# Multiple_Buck_Converter.net
KiCad netlist of a schematic drawn in Altium Designer
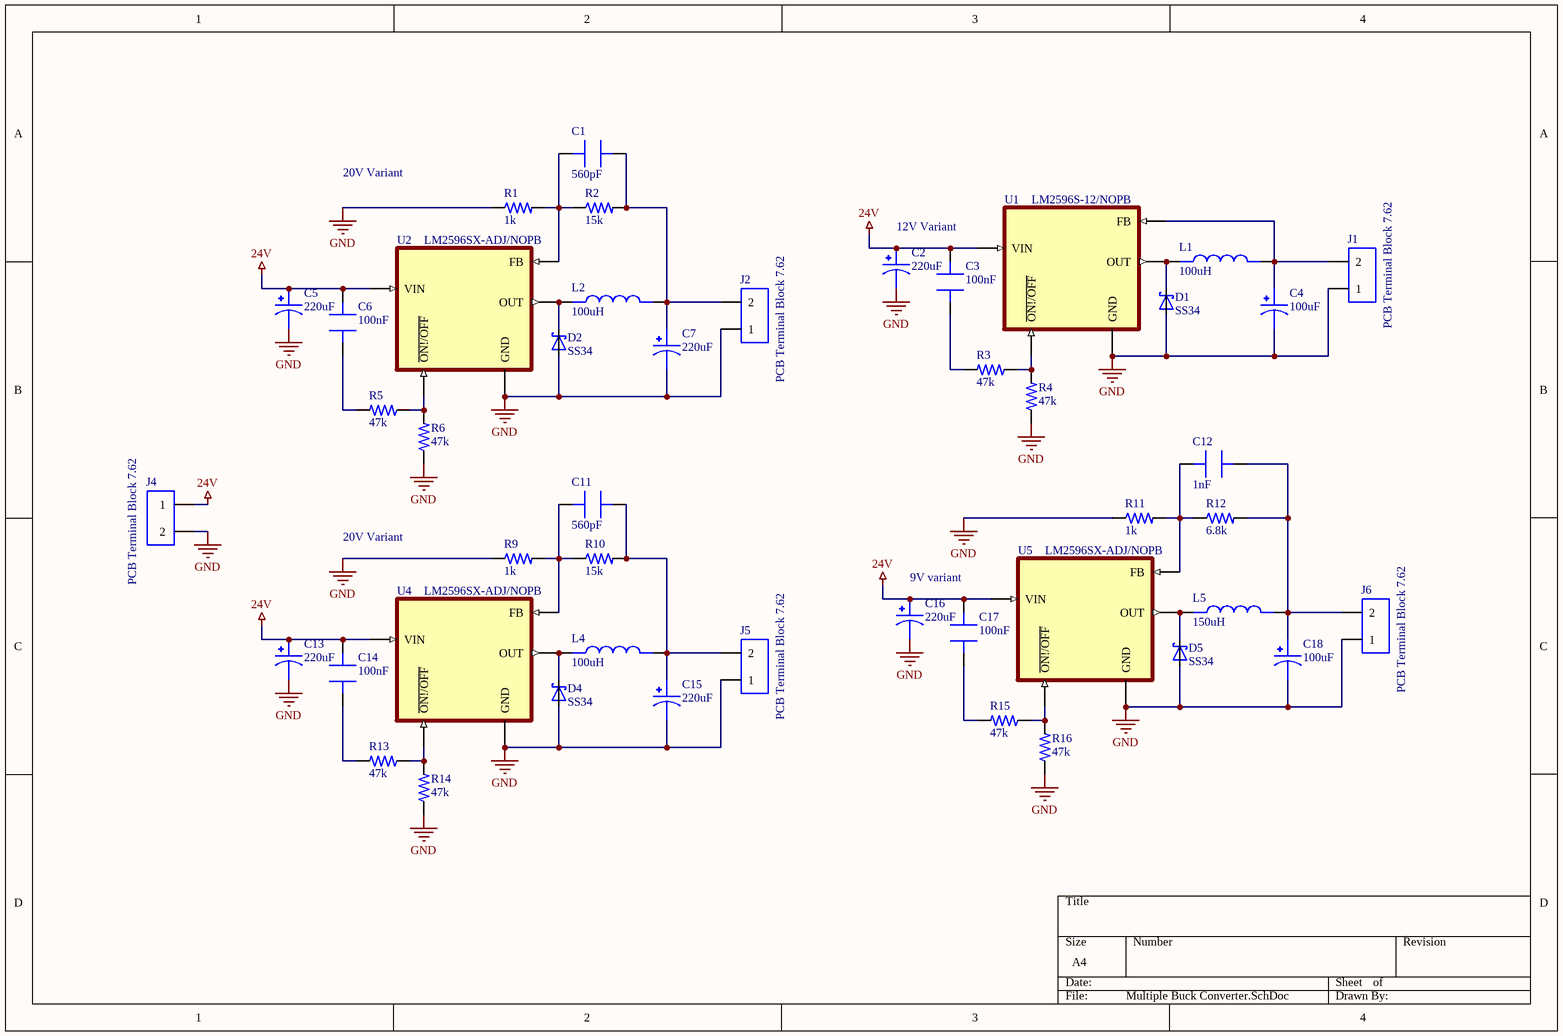
[diagram p0: Multiple Buck Converter.SchDoc]

(export (version "E")
  (design (tool "Eeschema 10.0.6"))
  (components
    (comp (ref "C1")
      (value "560pF")
      (footprint "C0805")
      (description "100V 560pF NP0 ±2% 0805 Multilayer Ceramic Capacitors MLCC - SMD/SMT ROHS")
      (fields
        (field (name "MANUFACTURER") "YAGEO")
        (field (name "MANUFACTURER PART NUMBER") "CC0805GRNPO0BN561")
      )
      (libsource (lib "Multiple Buck Converter") (part "CC0805GRNPO0BN561"))
    )
    (comp (ref "C2")
      (value "220uF")
      (footprint "CAPAE1030X1080N")
      (fields
        (field (name "MANUFACTURER") "Nichicon")
        (field (name "MANUFACTURER PART NUMBER") "UUD1H221MNL1GS")
      )
      (libsource (lib "Multiple Buck Converter") (part "UUD1H221MNL1GS"))
    )
    (comp (ref "C3")
      (value "100nF")
      (footprint "CAP_1206")
      (description "50V 100nF X7R ±10% 1206 Multilayer Ceramic Capacitors MLCC - SMD/SMT ROHS")
      (fields
        (field (name "MANUFACTURER") "YAGEO")
        (field (name "MANUFACTURER PART NUMBER") "CC1206KRX7R9BB104")
      )
      (libsource (lib "Multiple Buck Converter") (part "CC1206KRX7R9BB104"))
    )
    (comp (ref "C4")
      (value "100uF")
      (footprint "CAPPM7343X310N")
      (description "100uF 10V -55℃~+125℃ 50mΩ@100kHz ±10% CASE-D_7343 Tantalum Capacitors ROHS")
      (fields
        (field (name "MANUFACTURER") "Kyocera AVX")
        (field (name "MANUFACTURER PART NUMBER") "TPSD107K010R0050")
      )
      (libsource (lib "Multiple Buck Converter") (part "TPSD107K010R0050"))
    )
    (comp (ref "C5")
      (value "220uF")
      (footprint "CAPAE1030X1080N")
      (fields
        (field (name "MANUFACTURER") "Nichicon")
        (field (name "MANUFACTURER PART NUMBER") "UUD1H221MNL1GS")
      )
      (libsource (lib "Multiple Buck Converter") (part "UUD1H221MNL1GS"))
    )
    (comp (ref "C6")
      (value "100nF")
      (footprint "CAP_1206")
      (description "50V 100nF X7R ±10% 1206 Multilayer Ceramic Capacitors MLCC - SMD/SMT ROHS")
      (fields
        (field (name "MANUFACTURER") "YAGEO")
        (field (name "MANUFACTURER PART NUMBER") "CC1206KRX7R9BB104")
      )
      (libsource (lib "Multiple Buck Converter") (part "CC1206KRX7R9BB104"))
    )
    (comp (ref "C7")
      (value "220uF")
      (footprint "CAPAE1030X1080N")
      (fields
        (field (name "MANUFACTURER") "Nichicon")
        (field (name "MANUFACTURER PART NUMBER") "UUD1H221MNL1GS")
      )
      (libsource (lib "Multiple Buck Converter") (part "UUD1H221MNL1GS"))
    )
    (comp (ref "C11")
      (value "560pF")
      (footprint "C0805")
      (description "100V 560pF NP0 ±2% 0805 Multilayer Ceramic Capacitors MLCC - SMD/SMT ROHS")
      (fields
        (field (name "MANUFACTURER") "YAGEO")
        (field (name "MANUFACTURER PART NUMBER") "CC0805GRNPO0BN561")
      )
      (libsource (lib "Multiple Buck Converter") (part "CC0805GRNPO0BN561"))
    )
    (comp (ref "C12")
      (value "1nF")
      (footprint "CAP_1206")
      (description "2kV 1nF X7R ±10% 1206 Multilayer Ceramic Capacitors MLCC - SMD/SMT ROHS")
      (fields
        (field (name "MANUFACTURER") "YAGEO")
        (field (name "MANUFACTURER PART NUMBER") "CC1206KKX7RDBB102")
      )
      (libsource (lib "Multiple Buck Converter") (part "CC1206KKX7RDBB102"))
    )
    (comp (ref "C13")
      (value "220uF")
      (footprint "CAPAE1030X1080N")
      (fields
        (field (name "MANUFACTURER") "Nichicon")
        (field (name "MANUFACTURER PART NUMBER") "UUD1H221MNL1GS")
      )
      (libsource (lib "Multiple Buck Converter") (part "UUD1H221MNL1GS"))
    )
    (comp (ref "C14")
      (value "100nF")
      (footprint "CAP_1206")
      (description "50V 100nF X7R ±10% 1206 Multilayer Ceramic Capacitors MLCC - SMD/SMT ROHS")
      (fields
        (field (name "MANUFACTURER") "YAGEO")
        (field (name "MANUFACTURER PART NUMBER") "CC1206KRX7R9BB104")
      )
      (libsource (lib "Multiple Buck Converter") (part "CC1206KRX7R9BB104"))
    )
    (comp (ref "C15")
      (value "220uF")
      (footprint "CAPAE1030X1080N")
      (fields
        (field (name "MANUFACTURER") "Nichicon")
        (field (name "MANUFACTURER PART NUMBER") "UUD1H221MNL1GS")
      )
      (libsource (lib "Multiple Buck Converter") (part "UUD1H221MNL1GS"))
    )
    (comp (ref "C16")
      (value "220uF")
      (footprint "CAPAE1030X1080N")
      (fields
        (field (name "MANUFACTURER") "Nichicon")
        (field (name "MANUFACTURER PART NUMBER") "UUD1H221MNL1GS")
      )
      (libsource (lib "Multiple Buck Converter") (part "UUD1H221MNL1GS"))
    )
    (comp (ref "C17")
      (value "100nF")
      (footprint "CAP_1206")
      (description "50V 100nF X7R ±10% 1206 Multilayer Ceramic Capacitors MLCC - SMD/SMT ROHS")
      (fields
        (field (name "MANUFACTURER") "YAGEO")
        (field (name "MANUFACTURER PART NUMBER") "CC1206KRX7R9BB104")
      )
      (libsource (lib "Multiple Buck Converter") (part "CC1206KRX7R9BB104"))
    )
    (comp (ref "C18")
      (value "100uF")
      (footprint "CAPPM6032X280N")
      (description "100uF 16V -55℃~+125℃ 1Ω@100kHz ±20% CASE-C_6032 Tantalum Capacitors ROHS")
      (fields
        (field (name "MANUFACTURER") "Hunan Xiangyee in S&T")
        (field (name "MANUFACTURER PART NUMBER") "CA45-C016M107T")
      )
      (libsource (lib "Multiple Buck Converter") (part "CA45-C016M107T"))
    )
    (comp (ref "D1")
      (value "SS34")
      (footprint "SS34-1")
      (description "0.5mA@40V 40V Single 3A 0.55V@3A SMA(DO-214AC) Schottky Barrier Diodes (SBD) ROHS")
      (fields (field (name "MANUFACTURER") "MDD (Microdiode Electronics)"))
      (libsource (lib "Multiple Buck Converter") (part "SS34"))
    )
    (comp (ref "D2")
      (value "SS34")
      (footprint "SS34-1")
      (description "0.5mA@40V 40V Single 3A 0.55V@3A SMA(DO-214AC) Schottky Barrier Diodes (SBD) ROHS")
      (fields (field (name "MANUFACTURER") "MDD (Microdiode Electronics)"))
      (libsource (lib "Multiple Buck Converter") (part "SS34"))
    )
    (comp (ref "D4")
      (value "SS34")
      (footprint "SS34-1")
      (description "0.5mA@40V 40V Single 3A 0.55V@3A SMA(DO-214AC) Schottky Barrier Diodes (SBD) ROHS")
      (fields (field (name "MANUFACTURER") "MDD (Microdiode Electronics)"))
      (libsource (lib "Multiple Buck Converter") (part "SS34"))
    )
    (comp (ref "D5")
      (value "SS34")
      (footprint "SS34-1")
      (description "0.5mA@40V 40V Single 3A 0.55V@3A SMA(DO-214AC) Schottky Barrier Diodes (SBD) ROHS")
      (fields (field (name "MANUFACTURER") "MDD (Microdiode Electronics)"))
      (libsource (lib "Multiple Buck Converter") (part "SS34"))
    )
    (comp (ref "J1")
      (value "PCB Terminal Block 7.62")
      (footprint "KF25C-7.62-2P")
      (fields
        (field (name "MANUFACTURER") "Cixi Kefa Elec")
        (field (name "MANUFACTURER PART NUMBER") "KF25C-7.62-2P")
      )
      (libsource (lib "Multiple Buck Converter") (part "KF25C-7.62-2P"))
    )
    (comp (ref "J2")
      (value "PCB Terminal Block 7.62")
      (footprint "KF25C-7.62-2P")
      (fields
        (field (name "MANUFACTURER") "Cixi Kefa Elec")
        (field (name "MANUFACTURER PART NUMBER") "KF25C-7.62-2P")
      )
      (libsource (lib "Multiple Buck Converter") (part "KF25C-7.62-2P"))
    )
    (comp (ref "J4")
      (value "PCB Terminal Block 7.62")
      (footprint "KF25C-7.62-2P")
      (fields
        (field (name "MANUFACTURER") "Cixi Kefa Elec")
        (field (name "MANUFACTURER PART NUMBER") "KF25C-7.62-2P")
      )
      (libsource (lib "Multiple Buck Converter") (part "KF25C-7.62-2P"))
    )
    (comp (ref "J5")
      (value "PCB Terminal Block 7.62")
      (footprint "KF25C-7.62-2P")
      (fields
        (field (name "MANUFACTURER") "Cixi Kefa Elec")
        (field (name "MANUFACTURER PART NUMBER") "KF25C-7.62-2P")
      )
      (libsource (lib "Multiple Buck Converter") (part "KF25C-7.62-2P"))
    )
    (comp (ref "J6")
      (value "PCB Terminal Block 7.62")
      (footprint "KF25C-7.62-2P")
      (fields
        (field (name "MANUFACTURER") "Cixi Kefa Elec")
        (field (name "MANUFACTURER PART NUMBER") "KF25C-7.62-2P")
      )
      (libsource (lib "Multiple Buck Converter") (part "KF25C-7.62-2P"))
    )
    (comp (ref "L1")
      (value "100uH")
      (footprint "DS1207")
      (description "Shielded Inductor DS1207 100uH")
      (fields (field (name "MANUFACTURER") "SPORTON") (field (name "MANUFACTURER PART NUMBER") "SDS127"))
      (libsource (lib "Multiple Buck Converter") (part "DS1207_100uH"))
    )
    (comp (ref "L2")
      (value "100uH")
      (footprint "DS1207")
      (description "Shielded Inductor DS1207 100uH")
      (fields (field (name "MANUFACTURER") "SPORTON") (field (name "MANUFACTURER PART NUMBER") "SDS127"))
      (libsource (lib "Multiple Buck Converter") (part "DS1207_100uH"))
    )
    (comp (ref "L4")
      (value "100uH")
      (footprint "DS1207")
      (description "Shielded Inductor DS1207 100uH")
      (fields (field (name "MANUFACTURER") "SPORTON") (field (name "MANUFACTURER PART NUMBER") "SDS127"))
      (libsource (lib "Multiple Buck Converter") (part "DS1207_100uH"))
    )
    (comp (ref "L5")
      (value "150uH")
      (footprint "DS1207")
      (description "Shielded Inductor DS1207 47uH")
      (fields (field (name "MANUFACTURER") "SPORTON") (field (name "MANUFACTURER PART NUMBER") "SDS127"))
      (libsource (lib "Multiple Buck Converter") (part "DS1207_150uH"))
    )
    (comp (ref "R1")
      (value "1k")
      (footprint "RES_1206")
      (fields
        (field (name "MANUFACTURER") "YAGEO")
        (field (name "MANUFACTURER PART NUMBER") "RC1206FR-071KL")
      )
      (libsource (lib "Multiple Buck Converter") (part "RC1206FR-071KL"))
    )
    (comp (ref "R2")
      (value "15k")
      (footprint "RES_1206")
      (fields
        (field (name "MANUFACTURER") "YAGEO")
        (field (name "MANUFACTURER PART NUMBER") "RC1206FR-0715KL")
      )
      (libsource (lib "Multiple Buck Converter") (part "RC1206FR-0715KL"))
    )
    (comp (ref "R3")
      (value "47k")
      (footprint "RES_1206")
      (fields
        (field (name "MANUFACTURER") "YAGEO")
        (field (name "MANUFACTURER PART NUMBER") "RC1206FR-0747KL")
      )
      (libsource (lib "Multiple Buck Converter") (part "RC1206FR-0747KL"))
    )
    (comp (ref "R4")
      (value "47k")
      (footprint "RES_1206")
      (fields
        (field (name "MANUFACTURER") "YAGEO")
        (field (name "MANUFACTURER PART NUMBER") "RC1206FR-0747KL")
      )
      (libsource (lib "Multiple Buck Converter") (part "RC1206FR-0747KL"))
    )
    (comp (ref "R5")
      (value "47k")
      (footprint "RES_1206")
      (fields
        (field (name "MANUFACTURER") "YAGEO")
        (field (name "MANUFACTURER PART NUMBER") "RC1206FR-0747KL")
      )
      (libsource (lib "Multiple Buck Converter") (part "RC1206FR-0747KL"))
    )
    (comp (ref "R6")
      (value "47k")
      (footprint "RES_1206")
      (fields
        (field (name "MANUFACTURER") "YAGEO")
        (field (name "MANUFACTURER PART NUMBER") "RC1206FR-0747KL")
      )
      (libsource (lib "Multiple Buck Converter") (part "RC1206FR-0747KL"))
    )
    (comp (ref "R9")
      (value "1k")
      (footprint "RES_1206")
      (fields
        (field (name "MANUFACTURER") "YAGEO")
        (field (name "MANUFACTURER PART NUMBER") "RC1206FR-071KL")
      )
      (libsource (lib "Multiple Buck Converter") (part "RC1206FR-071KL"))
    )
    (comp (ref "R10")
      (value "15k")
      (footprint "RES_1206")
      (fields
        (field (name "MANUFACTURER") "YAGEO")
        (field (name "MANUFACTURER PART NUMBER") "RC1206FR-0715KL")
      )
      (libsource (lib "Multiple Buck Converter") (part "RC1206FR-0715KL"))
    )
    (comp (ref "R11")
      (value "1k")
      (footprint "RES_1206")
      (fields
        (field (name "MANUFACTURER") "YAGEO")
        (field (name "MANUFACTURER PART NUMBER") "RC1206FR-071KL")
      )
      (libsource (lib "Multiple Buck Converter") (part "RC1206FR-071KL"))
    )
    (comp (ref "R12")
      (value "6.8k")
      (footprint "RES_1206")
      (fields
        (field (name "MANUFACTURER") "YAGEO")
        (field (name "MANUFACTURER PART NUMBER") "RC1206FR-076K8L")
      )
      (libsource (lib "Multiple Buck Converter") (part "RC1206FR-076K8L"))
    )
    (comp (ref "R13")
      (value "47k")
      (footprint "RES_1206")
      (fields
        (field (name "MANUFACTURER") "YAGEO")
        (field (name "MANUFACTURER PART NUMBER") "RC1206FR-0747KL")
      )
      (libsource (lib "Multiple Buck Converter") (part "RC1206FR-0747KL"))
    )
    (comp (ref "R14")
      (value "47k")
      (footprint "RES_1206")
      (fields
        (field (name "MANUFACTURER") "YAGEO")
        (field (name "MANUFACTURER PART NUMBER") "RC1206FR-0747KL")
      )
      (libsource (lib "Multiple Buck Converter") (part "RC1206FR-0747KL"))
    )
    (comp (ref "R15")
      (value "47k")
      (footprint "RES_1206")
      (fields
        (field (name "MANUFACTURER") "YAGEO")
        (field (name "MANUFACTURER PART NUMBER") "RC1206FR-0747KL")
      )
      (libsource (lib "Multiple Buck Converter") (part "RC1206FR-0747KL"))
    )
    (comp (ref "R16")
      (value "47k")
      (footprint "RES_1206")
      (fields
        (field (name "MANUFACTURER") "YAGEO")
        (field (name "MANUFACTURER PART NUMBER") "RC1206FR-0747KL")
      )
      (libsource (lib "Multiple Buck Converter") (part "RC1206FR-0747KL"))
    )
    (comp (ref "U1")
      (value "LM2596S-12/NOPB")
      (footprint "VREG_LM2596SX-ADJ/NOPB")
      (fields (field (name "MANUFACTURER") "Texas Instruments"))
      (libsource (lib "Multiple Buck Converter") (part "LM2596SX-ADJ/NOPB"))
    )
    (comp (ref "U2")
      (value "LM2596SX-ADJ/NOPB")
      (footprint "VREG_LM2596SX-ADJ/NOPB")
      (fields
        (field (name "MANUFACTURER") "UMW(Youtai Semiconductor Co., Ltd.)")
        (field (name "MANUFACTURER PART NUMBER") "LM2596S-ADJ")
      )
      (libsource (lib "Multiple Buck Converter") (part "LM2596SX-ADJ/NOPB"))
    )
    (comp (ref "U4")
      (value "LM2596SX-ADJ/NOPB")
      (footprint "VREG_LM2596SX-ADJ/NOPB")
      (fields
        (field (name "MANUFACTURER") "UMW(Youtai Semiconductor Co., Ltd.)")
        (field (name "MANUFACTURER PART NUMBER") "LM2596S-ADJ")
      )
      (libsource (lib "Multiple Buck Converter") (part "LM2596SX-ADJ/NOPB"))
    )
    (comp (ref "U5")
      (value "LM2596SX-ADJ/NOPB")
      (footprint "VREG_LM2596SX-ADJ/NOPB")
      (fields
        (field (name "MANUFACTURER") "UMW(Youtai Semiconductor Co., Ltd.)")
        (field (name "MANUFACTURER PART NUMBER") "LM2596S-ADJ")
      )
      (libsource (lib "Multiple Buck Converter") (part "LM2596SX-ADJ/NOPB"))
    )
  )
  (nets
    (net (code "1") (name "24V") (class "Default")
      (node (ref "C13") (pin "1") (pinfunction "1_1") (pintype "passive"))
      (node (ref "C14") (pin "1") (pinfunction "PIN1_1") (pintype "passive"))
      (node (ref "C16") (pin "1") (pinfunction "1_1") (pintype "passive"))
      (node (ref "C17") (pin "1") (pinfunction "PIN1_1") (pintype "passive"))
      (node (ref "C2") (pin "1") (pinfunction "1_1") (pintype "passive"))
      (node (ref "C3") (pin "1") (pinfunction "PIN1_1") (pintype "passive"))
      (node (ref "C5") (pin "1") (pinfunction "1_1") (pintype "passive"))
      (node (ref "C6") (pin "1") (pinfunction "PIN1_1") (pintype "passive"))
      (node (ref "J4") (pin "1") (pinfunction "1_1") (pintype "passive"))
      (node (ref "U1") (pin "1") (pinfunction "VIN_1") (pintype "input"))
      (node (ref "U2") (pin "1") (pinfunction "VIN_1") (pintype "input"))
      (node (ref "U4") (pin "1") (pinfunction "VIN_1") (pintype "input"))
      (node (ref "U5") (pin "1") (pinfunction "VIN_1") (pintype "input"))
    )
    (net (code "2") (name "GND") (class "Default")
      (node (ref "C13") (pin "2") (pinfunction "2_2") (pintype "passive"))
      (node (ref "C15") (pin "2") (pinfunction "2_2") (pintype "passive"))
      (node (ref "C16") (pin "2") (pinfunction "2_2") (pintype "passive"))
      (node (ref "C18") (pin "2") (pinfunction "2_2") (pintype "passive"))
      (node (ref "C2") (pin "2") (pinfunction "2_2") (pintype "passive"))
      (node (ref "C4") (pin "2") (pinfunction "2_2") (pintype "passive"))
      (node (ref "C5") (pin "2") (pinfunction "2_2") (pintype "passive"))
      (node (ref "C7") (pin "2") (pinfunction "2_2") (pintype "passive"))
      (node (ref "D1") (pin "A") (pinfunction "A_A") (pintype "passive"))
      (node (ref "D2") (pin "A") (pinfunction "A_A") (pintype "passive"))
      (node (ref "D4") (pin "A") (pinfunction "A_A") (pintype "passive"))
      (node (ref "D5") (pin "A") (pinfunction "A_A") (pintype "passive"))
      (node (ref "J1") (pin "1") (pinfunction "1_1") (pintype "passive"))
      (node (ref "J2") (pin "1") (pinfunction "1_1") (pintype "passive"))
      (node (ref "J4") (pin "2") (pinfunction "2_2") (pintype "passive"))
      (node (ref "J5") (pin "1") (pinfunction "1_1") (pintype "passive"))
      (node (ref "J6") (pin "1") (pinfunction "1_1") (pintype "passive"))
      (node (ref "R1") (pin "1") (pinfunction "1_1") (pintype "passive"))
      (node (ref "R11") (pin "1") (pinfunction "1_1") (pintype "passive"))
      (node (ref "R14") (pin "1") (pinfunction "1_1") (pintype "passive"))
      (node (ref "R16") (pin "1") (pinfunction "1_1") (pintype "passive"))
      (node (ref "R4") (pin "1") (pinfunction "1_1") (pintype "passive"))
      (node (ref "R6") (pin "1") (pinfunction "1_1") (pintype "passive"))
      (node (ref "R9") (pin "1") (pinfunction "1_1") (pintype "passive"))
      (node (ref "U1") (pin "3") (pinfunction "GND_3") (pintype "power_in"))
      (node (ref "U2") (pin "3") (pinfunction "GND_3") (pintype "power_in"))
      (node (ref "U4") (pin "3") (pinfunction "GND_3") (pintype "power_in"))
      (node (ref "U5") (pin "3") (pinfunction "GND_3") (pintype "power_in"))
    )
    (net (code "3") (name "Net-(C1-PIN1)") (class "Default")
      (node (ref "C1") (pin "1") (pinfunction "PIN1_1") (pintype "passive"))
      (node (ref "C7") (pin "1") (pinfunction "1_1") (pintype "passive"))
      (node (ref "J2") (pin "2") (pinfunction "2_2") (pintype "passive"))
      (node (ref "L2") (pin "2") (pinfunction "2_2") (pintype "passive"))
      (node (ref "R2") (pin "2") (pinfunction "2_2") (pintype "passive"))
    )
    (net (code "4") (name "Net-(C1-PIN2)") (class "Default")
      (node (ref "C1") (pin "2") (pinfunction "PIN2_2") (pintype "passive"))
      (node (ref "R1") (pin "2") (pinfunction "2_2") (pintype "passive"))
      (node (ref "R2") (pin "1") (pinfunction "1_1") (pintype "passive"))
      (node (ref "U2") (pin "4") (pinfunction "FB_4") (pintype "input"))
    )
    (net (code "5") (name "Net-(C3-PIN2)") (class "Default")
      (node (ref "C3") (pin "2") (pinfunction "PIN2_2") (pintype "passive"))
      (node (ref "R3") (pin "2") (pinfunction "2_2") (pintype "passive"))
    )
    (net (code "6") (name "Net-(C6-PIN2)") (class "Default")
      (node (ref "C6") (pin "2") (pinfunction "PIN2_2") (pintype "passive"))
      (node (ref "R5") (pin "2") (pinfunction "2_2") (pintype "passive"))
    )
    (net (code "7") (name "Net-(C11-PIN1)") (class "Default")
      (node (ref "C11") (pin "1") (pinfunction "PIN1_1") (pintype "passive"))
      (node (ref "C15") (pin "1") (pinfunction "1_1") (pintype "passive"))
      (node (ref "J5") (pin "2") (pinfunction "2_2") (pintype "passive"))
      (node (ref "L4") (pin "2") (pinfunction "2_2") (pintype "passive"))
      (node (ref "R10") (pin "2") (pinfunction "2_2") (pintype "passive"))
    )
    (net (code "8") (name "Net-(C11-PIN2)") (class "Default")
      (node (ref "C11") (pin "2") (pinfunction "PIN2_2") (pintype "passive"))
      (node (ref "R10") (pin "1") (pinfunction "1_1") (pintype "passive"))
      (node (ref "R9") (pin "2") (pinfunction "2_2") (pintype "passive"))
      (node (ref "U4") (pin "4") (pinfunction "FB_4") (pintype "input"))
    )
    (net (code "9") (name "Net-(C12-PIN1)") (class "Default")
      (node (ref "C12") (pin "1") (pinfunction "PIN1_1") (pintype "passive"))
      (node (ref "C18") (pin "1") (pinfunction "1_1") (pintype "passive"))
      (node (ref "J6") (pin "2") (pinfunction "2_2") (pintype "passive"))
      (node (ref "L5") (pin "2") (pinfunction "2_2") (pintype "passive"))
      (node (ref "R12") (pin "2") (pinfunction "2_2") (pintype "passive"))
    )
    (net (code "10") (name "Net-(C12-PIN2)") (class "Default")
      (node (ref "C12") (pin "2") (pinfunction "PIN2_2") (pintype "passive"))
      (node (ref "R11") (pin "2") (pinfunction "2_2") (pintype "passive"))
      (node (ref "R12") (pin "1") (pinfunction "1_1") (pintype "passive"))
      (node (ref "U5") (pin "4") (pinfunction "FB_4") (pintype "input"))
    )
    (net (code "11") (name "Net-(C14-PIN2)") (class "Default")
      (node (ref "C14") (pin "2") (pinfunction "PIN2_2") (pintype "passive"))
      (node (ref "R13") (pin "2") (pinfunction "2_2") (pintype "passive"))
    )
    (net (code "12") (name "Net-(C17-PIN2)") (class "Default")
      (node (ref "C17") (pin "2") (pinfunction "PIN2_2") (pintype "passive"))
      (node (ref "R15") (pin "2") (pinfunction "2_2") (pintype "passive"))
    )
    (net (code "13") (name "Net-(U1-FB)") (class "Default")
      (node (ref "C4") (pin "1") (pinfunction "1_1") (pintype "passive"))
      (node (ref "J1") (pin "2") (pinfunction "2_2") (pintype "passive"))
      (node (ref "L1") (pin "2") (pinfunction "2_2") (pintype "passive"))
      (node (ref "U1") (pin "4") (pinfunction "FB_4") (pintype "input"))
    )
    (net (code "14") (name "Net-(U1-OUT)") (class "Default")
      (node (ref "D1") (pin "C") (pinfunction "C_C") (pintype "passive"))
      (node (ref "L1") (pin "1") (pinfunction "1_1") (pintype "passive"))
      (node (ref "U1") (pin "2") (pinfunction "OUT_2") (pintype "output"))
    )
    (net (code "15") (name "Net-(U1-~{ON!{slash}OFF})") (class "Default")
      (node (ref "R3") (pin "1") (pinfunction "1_1") (pintype "passive"))
      (node (ref "R4") (pin "2") (pinfunction "2_2") (pintype "passive"))
      (node (ref "U1") (pin "5") (pinfunction "~{ON!/OFF}_5") (pintype "input"))
    )
    (net (code "16") (name "Net-(U2-OUT)") (class "Default")
      (node (ref "D2") (pin "C") (pinfunction "C_C") (pintype "passive"))
      (node (ref "L2") (pin "1") (pinfunction "1_1") (pintype "passive"))
      (node (ref "U2") (pin "2") (pinfunction "OUT_2") (pintype "output"))
    )
    (net (code "17") (name "Net-(U2-~{ON!{slash}OFF})") (class "Default")
      (node (ref "R5") (pin "1") (pinfunction "1_1") (pintype "passive"))
      (node (ref "R6") (pin "2") (pinfunction "2_2") (pintype "passive"))
      (node (ref "U2") (pin "5") (pinfunction "~{ON!/OFF}_5") (pintype "input"))
    )
    (net (code "18") (name "Net-(U4-OUT)") (class "Default")
      (node (ref "D4") (pin "C") (pinfunction "C_C") (pintype "passive"))
      (node (ref "L4") (pin "1") (pinfunction "1_1") (pintype "passive"))
      (node (ref "U4") (pin "2") (pinfunction "OUT_2") (pintype "output"))
    )
    (net (code "19") (name "Net-(U4-~{ON!{slash}OFF})") (class "Default")
      (node (ref "R13") (pin "1") (pinfunction "1_1") (pintype "passive"))
      (node (ref "R14") (pin "2") (pinfunction "2_2") (pintype "passive"))
      (node (ref "U4") (pin "5") (pinfunction "~{ON!/OFF}_5") (pintype "input"))
    )
    (net (code "20") (name "Net-(U5-OUT)") (class "Default")
      (node (ref "D5") (pin "C") (pinfunction "C_C") (pintype "passive"))
      (node (ref "L5") (pin "1") (pinfunction "1_1") (pintype "passive"))
      (node (ref "U5") (pin "2") (pinfunction "OUT_2") (pintype "output"))
    )
    (net (code "21") (name "Net-(U5-~{ON!{slash}OFF})") (class "Default")
      (node (ref "R15") (pin "1") (pinfunction "1_1") (pintype "passive"))
      (node (ref "R16") (pin "2") (pinfunction "2_2") (pintype "passive"))
      (node (ref "U5") (pin "5") (pinfunction "~{ON!/OFF}_5") (pintype "input"))
    )
  )
)
